# Filters.net
KiCad netlist of a schematic drawn in EAGLE
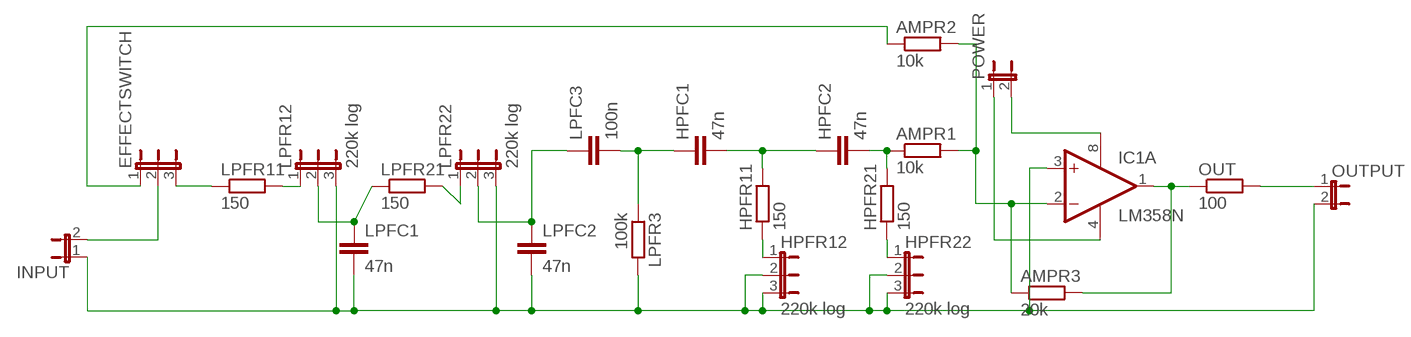
[diagram p0: schematic, sheet 1]

(export (version "E")
  (design (tool "Eeschema 10.0.6"))
  (components
    (comp (ref "AMPR1")
      (value "10k")
      (footprint "eagle-import:0207_10")
      (libsource (lib "eagle-import") (part "R-EU_0207/10"))
    )
    (comp (ref "AMPR2")
      (value "10k")
      (footprint "eagle-import:0207_10")
      (libsource (lib "eagle-import") (part "R-EU_0207/10"))
    )
    (comp (ref "AMPR3")
      (value "20k")
      (footprint "eagle-import:0207_10")
      (libsource (lib "eagle-import") (part "R-EU_0207/10"))
    )
    (comp (ref "EFFECTSWITCH")
      (value "220k log")
      (footprint "eagle-import:JP2")
      (libsource (lib "eagle-import") (part "JP2E"))
    )
    (comp (ref "HPFC1")
      (value "47n")
      (footprint "eagle-import:C025-025X050")
      (libsource (lib "eagle-import") (part "C-EU025-025X050"))
    )
    (comp (ref "HPFC2")
      (value "47n")
      (footprint "eagle-import:C025-025X050")
      (libsource (lib "eagle-import") (part "C-EU025-025X050"))
    )
    (comp (ref "HPFR11")
      (value "150")
      (footprint "eagle-import:0207_10")
      (libsource (lib "eagle-import") (part "R-EU_0207/10"))
    )
    (comp (ref "HPFR12")
      (value "220k log")
      (footprint "eagle-import:JP2")
      (libsource (lib "eagle-import") (part "JP2E"))
    )
    (comp (ref "HPFR21")
      (value "150")
      (footprint "eagle-import:0207_10")
      (libsource (lib "eagle-import") (part "R-EU_0207/10"))
    )
    (comp (ref "HPFR22")
      (value "220k log")
      (footprint "eagle-import:JP2")
      (libsource (lib "eagle-import") (part "JP2E"))
    )
    (comp (ref "IC1")
      (value "LM358N")
      (footprint "eagle-import:DIL08")
      (libsource (lib "eagle-import") (part "LM358N"))
    )
    (comp (ref "INPUT")
      (value "JP1E")
      (footprint "eagle-import:JP1")
      (libsource (lib "eagle-import") (part "JP1E"))
    )
    (comp (ref "LPFC1")
      (value "47n")
      (footprint "eagle-import:C025-025X050")
      (libsource (lib "eagle-import") (part "C-EU025-025X050"))
    )
    (comp (ref "LPFC2")
      (value "47n")
      (footprint "eagle-import:C025-025X050")
      (libsource (lib "eagle-import") (part "C-EU025-025X050"))
    )
    (comp (ref "LPFC3")
      (value "100n")
      (footprint "eagle-import:C025-025X050")
      (libsource (lib "eagle-import") (part "C-EU025-025X050"))
    )
    (comp (ref "LPFR3")
      (value "100k")
      (footprint "eagle-import:0207_10")
      (libsource (lib "eagle-import") (part "R-EU_0207/10"))
    )
    (comp (ref "LPFR11")
      (value "150")
      (footprint "eagle-import:0207_10")
      (libsource (lib "eagle-import") (part "R-EU_0207/10"))
    )
    (comp (ref "LPFR12")
      (value "220k log")
      (footprint "eagle-import:JP2")
      (libsource (lib "eagle-import") (part "JP2E"))
    )
    (comp (ref "LPFR21")
      (value "150")
      (footprint "eagle-import:0207_10")
      (libsource (lib "eagle-import") (part "R-EU_0207/10"))
    )
    (comp (ref "LPFR22")
      (value "220k log")
      (footprint "eagle-import:JP2")
      (libsource (lib "eagle-import") (part "JP2E"))
    )
    (comp (ref "OUT")
      (value "100")
      (footprint "eagle-import:0207_10")
      (libsource (lib "eagle-import") (part "R-EU_0207/10"))
    )
    (comp (ref "OUTPUT")
      (value "JP1E")
      (footprint "eagle-import:JP1")
      (libsource (lib "eagle-import") (part "JP1E"))
    )
    (comp (ref "POWER")
      (value "JP1E")
      (footprint "eagle-import:JP1")
      (libsource (lib "eagle-import") (part "JP1E"))
    )
  )
  (nets
    (net (code "1") (name "Net-(AMPR1-Pad1)") (class "Default")
      (node (ref "AMPR1") (pin "1") (pinfunction "1_1") (pintype "passive"))
      (node (ref "HPFC2") (pin "2") (pinfunction "2_2") (pintype "passive"))
      (node (ref "HPFR21") (pin "2") (pinfunction "2_2") (pintype "passive"))
    )
    (net (code "2") (name "Net-(AMPR2-Pad1)") (class "Default")
      (node (ref "AMPR2") (pin "1") (pinfunction "1_1") (pintype "passive"))
      (node (ref "EFFECTSWITCH") (pin "1") (pinfunction "1_1") (pintype "passive"))
    )
    (net (code "3") (name "Net-(EFFECTSWITCH-Pad2)") (class "Default")
      (node (ref "EFFECTSWITCH") (pin "2") (pinfunction "2_2") (pintype "passive"))
      (node (ref "INPUT") (pin "2") (pinfunction "2_2") (pintype "passive"))
    )
    (net (code "4") (name "Net-(EFFECTSWITCH-Pad3)") (class "Default")
      (node (ref "EFFECTSWITCH") (pin "3") (pinfunction "3_3") (pintype "passive"))
      (node (ref "LPFR11") (pin "1") (pinfunction "1_1") (pintype "passive"))
    )
    (net (code "5") (name "Net-(HPFC1-Pad1)") (class "Default")
      (node (ref "HPFC1") (pin "1") (pinfunction "1_1") (pintype "passive"))
      (node (ref "LPFC3") (pin "2") (pinfunction "2_2") (pintype "passive"))
      (node (ref "LPFR3") (pin "1") (pinfunction "1_1") (pintype "passive"))
    )
    (net (code "6") (name "Net-(HPFC1-Pad2)") (class "Default")
      (node (ref "HPFC1") (pin "2") (pinfunction "2_2") (pintype "passive"))
      (node (ref "HPFC2") (pin "1") (pinfunction "1_1") (pintype "passive"))
      (node (ref "HPFR11") (pin "2") (pinfunction "2_2") (pintype "passive"))
    )
    (net (code "7") (name "Net-(HPFR11-Pad1)") (class "Default")
      (node (ref "HPFR11") (pin "1") (pinfunction "1_1") (pintype "passive"))
      (node (ref "HPFR12") (pin "1") (pinfunction "1_1") (pintype "passive"))
    )
    (net (code "8") (name "Net-(HPFR21-Pad1)") (class "Default")
      (node (ref "HPFR21") (pin "1") (pinfunction "1_1") (pintype "passive"))
      (node (ref "HPFR22") (pin "1") (pinfunction "1_1") (pintype "passive"))
    )
    (net (code "9") (name "Net-(IC1A-+IN)") (class "Default")
      (node (ref "HPFR12") (pin "2") (pinfunction "2_2") (pintype "passive"))
      (node (ref "HPFR12") (pin "3") (pinfunction "3_3") (pintype "passive"))
      (node (ref "HPFR22") (pin "2") (pinfunction "2_2") (pintype "passive"))
      (node (ref "HPFR22") (pin "3") (pinfunction "3_3") (pintype "passive"))
      (node (ref "IC1") (pin "3") (pinfunction "+IN_3") (pintype "input"))
      (node (ref "INPUT") (pin "1") (pinfunction "1_1") (pintype "passive"))
      (node (ref "LPFC1") (pin "2") (pinfunction "2_2") (pintype "passive"))
      (node (ref "LPFC2") (pin "2") (pinfunction "2_2") (pintype "passive"))
      (node (ref "LPFR12") (pin "3") (pinfunction "3_3") (pintype "passive"))
      (node (ref "LPFR22") (pin "3") (pinfunction "3_3") (pintype "passive"))
      (node (ref "LPFR3") (pin "2") (pinfunction "2_2") (pintype "passive"))
      (node (ref "OUTPUT") (pin "2") (pinfunction "2_2") (pintype "passive"))
    )
    (net (code "10") (name "Net-(IC1A--IN)") (class "Default")
      (node (ref "AMPR1") (pin "2") (pinfunction "2_2") (pintype "passive"))
      (node (ref "AMPR2") (pin "2") (pinfunction "2_2") (pintype "passive"))
      (node (ref "AMPR3") (pin "1") (pinfunction "1_1") (pintype "passive"))
      (node (ref "IC1") (pin "2") (pinfunction "-IN_2") (pintype "input"))
    )
    (net (code "11") (name "Net-(IC1A-OUT)") (class "Default")
      (node (ref "AMPR3") (pin "2") (pinfunction "2_2") (pintype "passive"))
      (node (ref "IC1") (pin "1") (pinfunction "OUT_1") (pintype "output"))
      (node (ref "OUT") (pin "1") (pinfunction "1_1") (pintype "passive"))
    )
    (net (code "12") (name "Net-(IC1C-V+)") (class "Default")
      (node (ref "IC1") (pin "8") (pinfunction "V+_8") (pintype "power_in"))
      (node (ref "POWER") (pin "2") (pinfunction "2_2") (pintype "passive"))
    )
    (net (code "13") (name "Net-(IC1C-V-)") (class "Default")
      (node (ref "IC1") (pin "4") (pinfunction "V-_4") (pintype "power_in"))
      (node (ref "POWER") (pin "1") (pinfunction "1_1") (pintype "passive"))
    )
    (net (code "14") (name "Net-(LPFC1-Pad1)") (class "Default")
      (node (ref "LPFC1") (pin "1") (pinfunction "1_1") (pintype "passive"))
      (node (ref "LPFR12") (pin "2") (pinfunction "2_2") (pintype "passive"))
      (node (ref "LPFR21") (pin "1") (pinfunction "1_1") (pintype "passive"))
    )
    (net (code "15") (name "Net-(LPFC2-Pad1)") (class "Default")
      (node (ref "LPFC2") (pin "1") (pinfunction "1_1") (pintype "passive"))
      (node (ref "LPFC3") (pin "1") (pinfunction "1_1") (pintype "passive"))
      (node (ref "LPFR22") (pin "2") (pinfunction "2_2") (pintype "passive"))
    )
    (net (code "16") (name "Net-(LPFR11-Pad2)") (class "Default")
      (node (ref "LPFR11") (pin "2") (pinfunction "2_2") (pintype "passive"))
      (node (ref "LPFR12") (pin "1") (pinfunction "1_1") (pintype "passive"))
    )
    (net (code "17") (name "Net-(LPFR21-Pad2)") (class "Default")
      (node (ref "LPFR21") (pin "2") (pinfunction "2_2") (pintype "passive"))
      (node (ref "LPFR22") (pin "1") (pinfunction "1_1") (pintype "passive"))
    )
    (net (code "18") (name "Net-(OUT-Pad2)") (class "Default")
      (node (ref "OUT") (pin "2") (pinfunction "2_2") (pintype "passive"))
      (node (ref "OUTPUT") (pin "1") (pinfunction "1_1") (pintype "passive"))
    )
  )
)
